# FPGA.net
KiCad netlist of a schematic drawn in Altium Designer
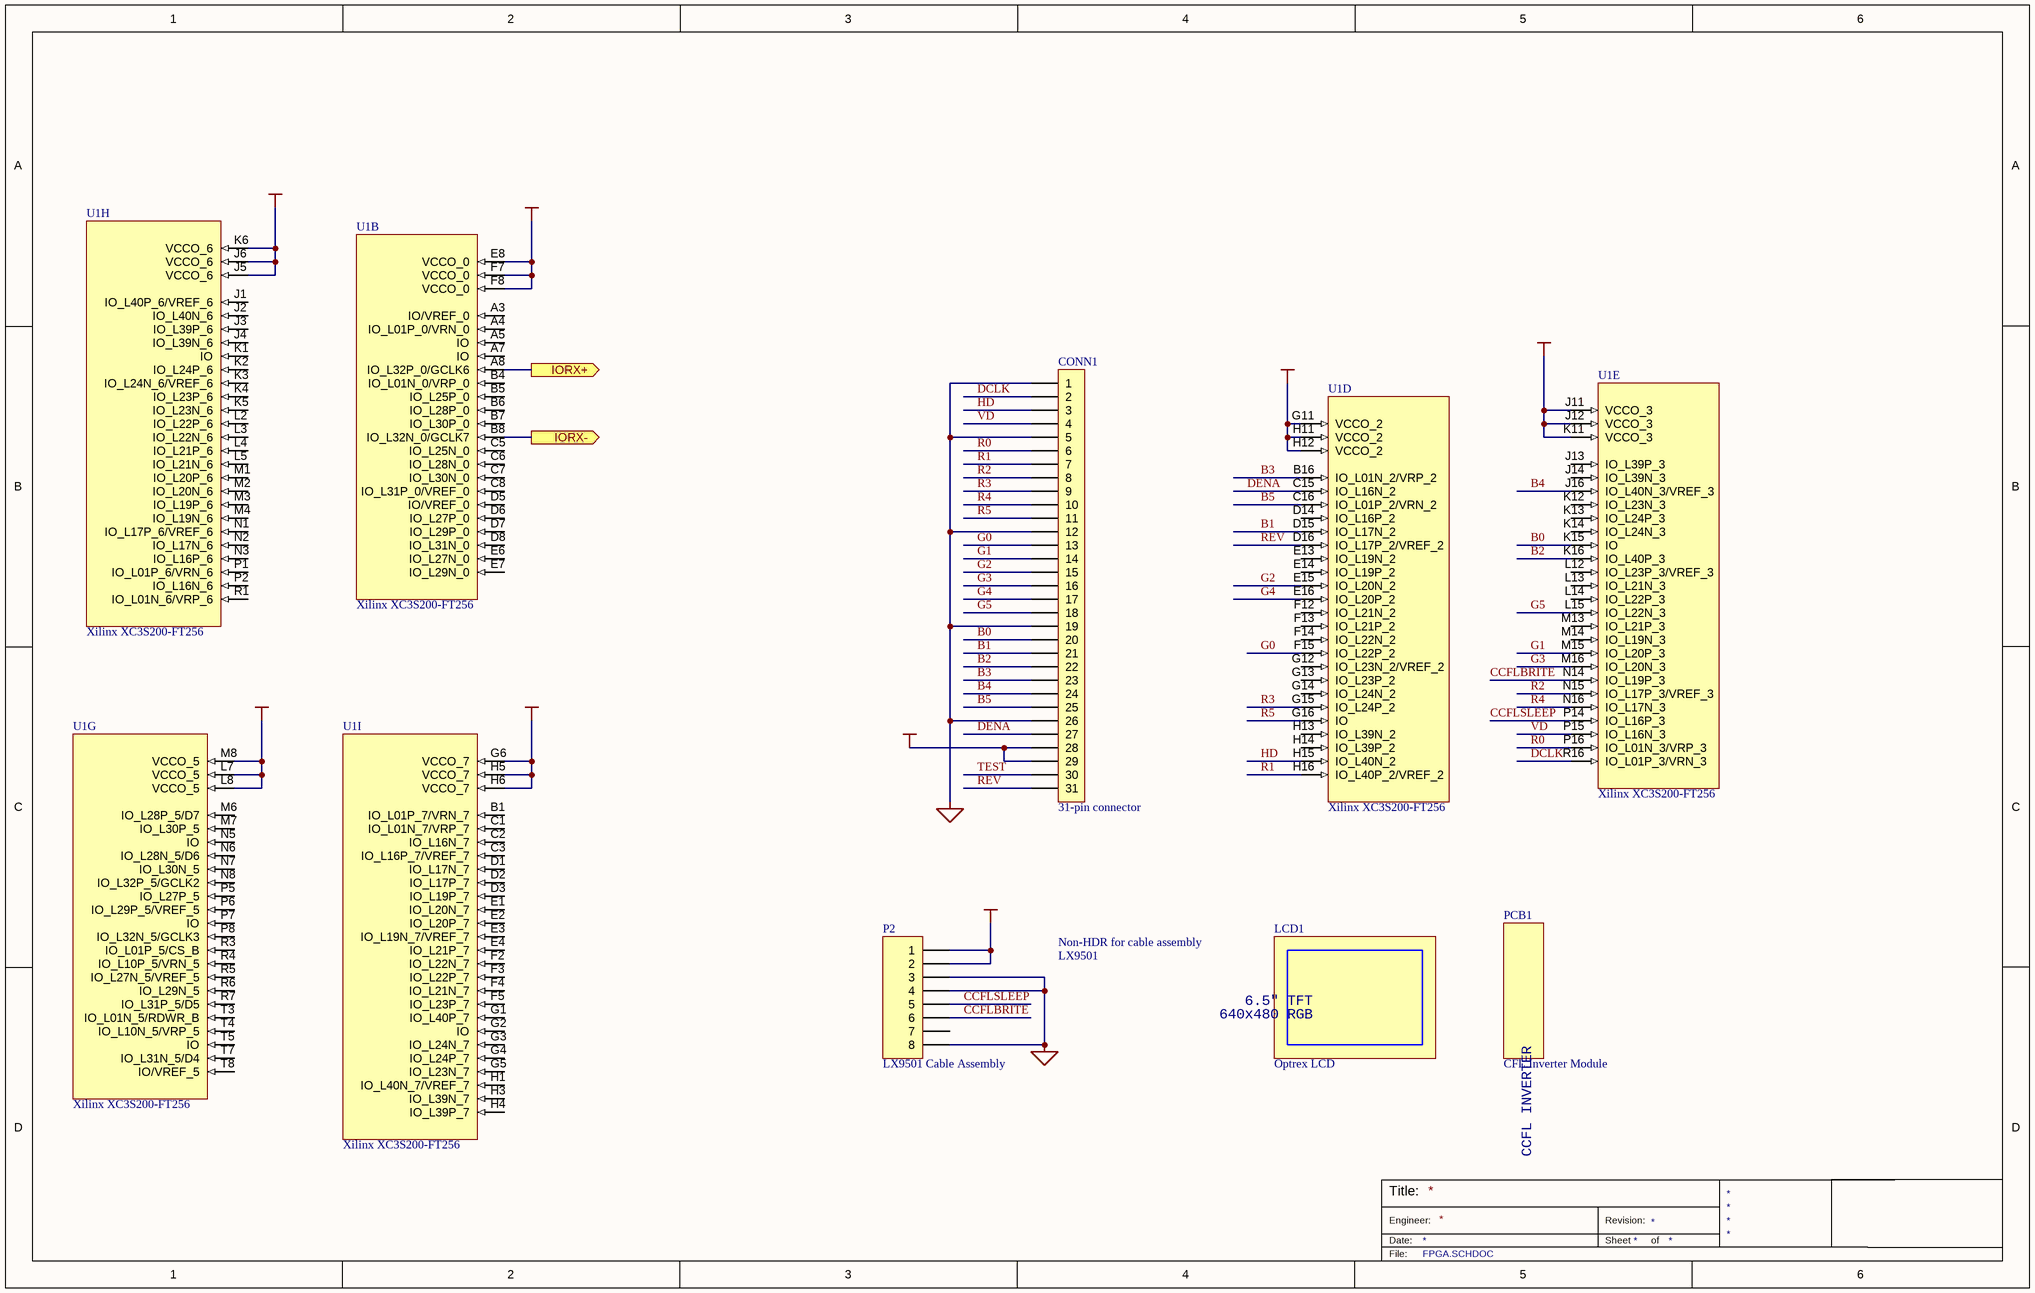
[diagram p0: FPGA.SCHDOC]

(export (version "E")
  (design (tool "Eeschema 10.0.6"))
  (components
    (comp (ref "CONN1")
      (value "31-pin connector")
      (footprint "DF9A-31S-1V")
      (libsource (lib "*") (part "CON31"))
    )
    (comp (ref "LCD1")
      (value "Optrex LCD")
      (description "Optrex 6.5\" 640x480 TFT")
      (libsource (lib "parts") (part "T-51750GD065J-FW-AA"))
    )
    (comp (ref "P2")
      (value "LX9501 Cable Assembly")
      (footprint "HDR1X8")
      (description "Header, 8-Pin")
      (fields (field (name "PUBLISHER") "Altium Limited"))
      (libsource (lib "Miscellaneous Connectors") (part "Header 8"))
    )
    (comp (ref "PCB1")
      (value "CFL Inverter Module")
      (description "4W 12V Inverter module for CCFL")
      (libsource (lib "parts") (part "LXM1623-12-41"))
    )
    (comp (ref "U1")
      (value "Xilinx XC3S200-FT256")
      (footprint "Xilinx FT256 BGA")
      (description "Xilinx Spartan-3 FPGA")
      (libsource (lib "parts") (part "XC3S200-FT256"))
    )
  )
  (nets
    (net (code "1") (name "+2.5VCC") (class "Default")
      (node (ref "U1") (pin "E8") (pinfunction "VCCO_0_E8") (pintype "input"))
      (node (ref "U1") (pin "F7") (pinfunction "VCCO_0_F7") (pintype "input"))
      (node (ref "U1") (pin "F8") (pinfunction "VCCO_0_F8") (pintype "input"))
    )
    (net (code "2") (name "+12VCC") (class "Default")
      (node (ref "P2") (pin "1") (pinfunction "1_1") (pintype "passive"))
      (node (ref "P2") (pin "2") (pinfunction "2_2") (pintype "passive"))
    )
    (net (code "3") (name "/B0") (class "Default")
      (node (ref "CONN1") (pin "20") (pinfunction "20_20") (pintype "passive"))
      (node (ref "U1") (pin "K15") (pinfunction "IO_K15") (pintype "input"))
    )
    (net (code "4") (name "/B1") (class "Default")
      (node (ref "CONN1") (pin "21") (pinfunction "21_21") (pintype "passive"))
      (node (ref "U1") (pin "D15") (pinfunction "IO_L17N_2_D15") (pintype "input"))
    )
    (net (code "5") (name "/B2") (class "Default")
      (node (ref "CONN1") (pin "22") (pinfunction "22_22") (pintype "passive"))
      (node (ref "U1") (pin "K16") (pinfunction "IO_L40P_3_K16") (pintype "input"))
    )
    (net (code "6") (name "/B3") (class "Default")
      (node (ref "CONN1") (pin "23") (pinfunction "23_23") (pintype "passive"))
      (node (ref "U1") (pin "B16") (pinfunction "IO_L01N_2/VRP_2_B16") (pintype "input"))
    )
    (net (code "7") (name "/B4") (class "Default")
      (node (ref "CONN1") (pin "24") (pinfunction "24_24") (pintype "passive"))
      (node (ref "U1") (pin "J16") (pinfunction "IO_L40N_3/VREF_3_J16") (pintype "input"))
    )
    (net (code "8") (name "/B5") (class "Default")
      (node (ref "CONN1") (pin "25") (pinfunction "25_25") (pintype "passive"))
      (node (ref "U1") (pin "C16") (pinfunction "IO_L01P_2/VRN_2_C16") (pintype "input"))
    )
    (net (code "9") (name "/CCFLBRITE") (class "Default")
      (node (ref "P2") (pin "6") (pinfunction "6_6") (pintype "passive"))
      (node (ref "U1") (pin "N14") (pinfunction "IO_L19P_3_N14") (pintype "input"))
    )
    (net (code "10") (name "/CCFLSLEEP") (class "Default")
      (node (ref "P2") (pin "5") (pinfunction "5_5") (pintype "passive"))
      (node (ref "U1") (pin "P14") (pinfunction "IO_L16P_3_P14") (pintype "input"))
    )
    (net (code "11") (name "/DCLK") (class "Default")
      (node (ref "CONN1") (pin "2") (pinfunction "2_2") (pintype "passive"))
      (node (ref "U1") (pin "R16") (pinfunction "IO_L01P_3/VRN_3_R16") (pintype "input"))
    )
    (net (code "12") (name "/DENA") (class "Default")
      (node (ref "CONN1") (pin "27") (pinfunction "27_27") (pintype "passive"))
      (node (ref "U1") (pin "C15") (pinfunction "IO_L16N_2_C15") (pintype "input"))
    )
    (net (code "13") (name "/G0") (class "Default")
      (node (ref "CONN1") (pin "13") (pinfunction "13_13") (pintype "passive"))
      (node (ref "U1") (pin "F15") (pinfunction "IO_L22P_2_F15") (pintype "input"))
    )
    (net (code "14") (name "/G1") (class "Default")
      (node (ref "CONN1") (pin "14") (pinfunction "14_14") (pintype "passive"))
      (node (ref "U1") (pin "M15") (pinfunction "IO_L20P_3_M15") (pintype "input"))
    )
    (net (code "15") (name "/G2") (class "Default")
      (node (ref "CONN1") (pin "15") (pinfunction "15_15") (pintype "passive"))
      (node (ref "U1") (pin "E15") (pinfunction "IO_L20N_2_E15") (pintype "input"))
    )
    (net (code "16") (name "/G3") (class "Default")
      (node (ref "CONN1") (pin "16") (pinfunction "16_16") (pintype "passive"))
      (node (ref "U1") (pin "M16") (pinfunction "IO_L20N_3_M16") (pintype "input"))
    )
    (net (code "17") (name "/G4") (class "Default")
      (node (ref "CONN1") (pin "17") (pinfunction "17_17") (pintype "passive"))
      (node (ref "U1") (pin "E16") (pinfunction "IO_L20P_2_E16") (pintype "input"))
    )
    (net (code "18") (name "/G5") (class "Default")
      (node (ref "CONN1") (pin "18") (pinfunction "18_18") (pintype "passive"))
      (node (ref "U1") (pin "L15") (pinfunction "IO_L22N_3_L15") (pintype "input"))
    )
    (net (code "19") (name "/HD") (class "Default")
      (node (ref "CONN1") (pin "3") (pinfunction "3_3") (pintype "passive"))
      (node (ref "U1") (pin "H15") (pinfunction "IO_L40N_2_H15") (pintype "input"))
    )
    (net (code "20") (name "/IORX+") (class "Default")
      (node (ref "U1") (pin "A8") (pinfunction "IO_L32P_0/GCLK6_A8") (pintype "input"))
    )
    (net (code "21") (name "/IORX-") (class "Default")
      (node (ref "U1") (pin "B8") (pinfunction "IO_L32N_0/GCLK7_B8") (pintype "input"))
    )
    (net (code "22") (name "/R0") (class "Default")
      (node (ref "CONN1") (pin "6") (pinfunction "6_6") (pintype "passive"))
      (node (ref "U1") (pin "P16") (pinfunction "IO_L01N_3/VRP_3_P16") (pintype "input"))
    )
    (net (code "23") (name "/R1") (class "Default")
      (node (ref "CONN1") (pin "7") (pinfunction "7_7") (pintype "passive"))
      (node (ref "U1") (pin "H16") (pinfunction "IO_L40P_2/VREF_2_H16") (pintype "input"))
    )
    (net (code "24") (name "/R2") (class "Default")
      (node (ref "CONN1") (pin "8") (pinfunction "8_8") (pintype "passive"))
      (node (ref "U1") (pin "N15") (pinfunction "IO_L17P_3/VREF_3_N15") (pintype "input"))
    )
    (net (code "25") (name "/R3") (class "Default")
      (node (ref "CONN1") (pin "9") (pinfunction "9_9") (pintype "passive"))
      (node (ref "U1") (pin "G15") (pinfunction "IO_L24P_2_G15") (pintype "input"))
    )
    (net (code "26") (name "/R4") (class "Default")
      (node (ref "CONN1") (pin "10") (pinfunction "10_10") (pintype "passive"))
      (node (ref "U1") (pin "N16") (pinfunction "IO_L17N_3_N16") (pintype "input"))
    )
    (net (code "27") (name "/R5") (class "Default")
      (node (ref "CONN1") (pin "11") (pinfunction "11_11") (pintype "passive"))
      (node (ref "U1") (pin "G16") (pinfunction "IO_G16") (pintype "input"))
    )
    (net (code "28") (name "/REV") (class "Default")
      (node (ref "CONN1") (pin "31") (pinfunction "31_31") (pintype "passive"))
      (node (ref "U1") (pin "D16") (pinfunction "IO_L17P_2/VREF_2_D16") (pintype "input"))
    )
    (net (code "29") (name "/TEST") (class "Default")
      (node (ref "CONN1") (pin "30") (pinfunction "30_30") (pintype "passive"))
    )
    (net (code "30") (name "/VD") (class "Default")
      (node (ref "CONN1") (pin "4") (pinfunction "4_4") (pintype "passive"))
      (node (ref "U1") (pin "P15") (pinfunction "IO_L16N_3_P15") (pintype "input"))
    )
    (net (code "31") (name "GND") (class "Default")
      (node (ref "CONN1") (pin "1") (pinfunction "1_1") (pintype "passive"))
      (node (ref "CONN1") (pin "12") (pinfunction "12_12") (pintype "passive"))
      (node (ref "CONN1") (pin "19") (pinfunction "19_19") (pintype "passive"))
      (node (ref "CONN1") (pin "26") (pinfunction "26_26") (pintype "passive"))
      (node (ref "CONN1") (pin "5") (pinfunction "5_5") (pintype "passive"))
      (node (ref "P2") (pin "3") (pinfunction "3_3") (pintype "passive"))
      (node (ref "P2") (pin "4") (pinfunction "4_4") (pintype "passive"))
      (node (ref "P2") (pin "8") (pinfunction "8_8") (pintype "passive"))
    )
    (net (code "32") (name "VCC") (class "Default")
      (node (ref "CONN1") (pin "28") (pinfunction "28_28") (pintype "passive"))
      (node (ref "CONN1") (pin "29") (pinfunction "29_29") (pintype "passive"))
      (node (ref "U1") (pin "G11") (pinfunction "VCCO_2_G11") (pintype "input"))
      (node (ref "U1") (pin "G6") (pinfunction "VCCO_7_G6") (pintype "input"))
      (node (ref "U1") (pin "H11") (pinfunction "VCCO_2_H11") (pintype "input"))
      (node (ref "U1") (pin "H12") (pinfunction "VCCO_2_H12") (pintype "input"))
      (node (ref "U1") (pin "H5") (pinfunction "VCCO_7_H5") (pintype "input"))
      (node (ref "U1") (pin "H6") (pinfunction "VCCO_7_H6") (pintype "input"))
      (node (ref "U1") (pin "J11") (pinfunction "VCCO_3_J11") (pintype "input"))
      (node (ref "U1") (pin "J12") (pinfunction "VCCO_3_J12") (pintype "input"))
      (node (ref "U1") (pin "J5") (pinfunction "VCCO_6_J5") (pintype "input"))
      (node (ref "U1") (pin "J6") (pinfunction "VCCO_6_J6") (pintype "input"))
      (node (ref "U1") (pin "K11") (pinfunction "VCCO_3_K11") (pintype "input"))
      (node (ref "U1") (pin "K6") (pinfunction "VCCO_6_K6") (pintype "input"))
      (node (ref "U1") (pin "L7") (pinfunction "VCCO_5_L7") (pintype "input"))
      (node (ref "U1") (pin "L8") (pinfunction "VCCO_5_L8") (pintype "input"))
      (node (ref "U1") (pin "M8") (pinfunction "VCCO_5_M8") (pintype "input"))
    )
    (net (code "33") (name "unconnected-(P2-Pad7)") (class "Default")
      (node (ref "P2") (pin "7") (pinfunction "7_7") (pintype "passive"))
    )
    (net (code "34") (name "unconnected-(U1B-IO-PadA5)") (class "Default")
      (node (ref "U1") (pin "A5") (pinfunction "IO_A5") (pintype "input"))
    )
    (net (code "35") (name "unconnected-(U1B-IO-PadA7)") (class "Default")
      (node (ref "U1") (pin "A7") (pinfunction "IO_A7") (pintype "input"))
    )
    (net (code "36") (name "unconnected-(U1B-IO_L01N_0{slash}VRP_0-PadB4)") (class "Default")
      (node (ref "U1") (pin "B4") (pinfunction "IO_L01N_0/VRP_0_B4") (pintype "input"))
    )
    (net (code "37") (name "unconnected-(U1B-IO_L01P_0{slash}VRN_0-PadA4)") (class "Default")
      (node (ref "U1") (pin "A4") (pinfunction "IO_L01P_0/VRN_0_A4") (pintype "input"))
    )
    (net (code "38") (name "unconnected-(U1B-IO_L25N_0-PadC5)") (class "Default")
      (node (ref "U1") (pin "C5") (pinfunction "IO_L25N_0_C5") (pintype "input"))
    )
    (net (code "39") (name "unconnected-(U1B-IO_L25P_0-PadB5)") (class "Default")
      (node (ref "U1") (pin "B5") (pinfunction "IO_L25P_0_B5") (pintype "input"))
    )
    (net (code "40") (name "unconnected-(U1B-IO_L27N_0-PadE6)") (class "Default")
      (node (ref "U1") (pin "E6") (pinfunction "IO_L27N_0_E6") (pintype "input"))
    )
    (net (code "41") (name "unconnected-(U1B-IO_L27P_0-PadD6)") (class "Default")
      (node (ref "U1") (pin "D6") (pinfunction "IO_L27P_0_D6") (pintype "input"))
    )
    (net (code "42") (name "unconnected-(U1B-IO_L28N_0-PadC6)") (class "Default")
      (node (ref "U1") (pin "C6") (pinfunction "IO_L28N_0_C6") (pintype "input"))
    )
    (net (code "43") (name "unconnected-(U1B-IO_L28P_0-PadB6)") (class "Default")
      (node (ref "U1") (pin "B6") (pinfunction "IO_L28P_0_B6") (pintype "input"))
    )
    (net (code "44") (name "unconnected-(U1B-IO_L29N_0-PadE7)") (class "Default")
      (node (ref "U1") (pin "E7") (pinfunction "IO_L29N_0_E7") (pintype "input"))
    )
    (net (code "45") (name "unconnected-(U1B-IO_L29P_0-PadD7)") (class "Default")
      (node (ref "U1") (pin "D7") (pinfunction "IO_L29P_0_D7") (pintype "input"))
    )
    (net (code "46") (name "unconnected-(U1B-IO_L30N_0-PadC7)") (class "Default")
      (node (ref "U1") (pin "C7") (pinfunction "IO_L30N_0_C7") (pintype "input"))
    )
    (net (code "47") (name "unconnected-(U1B-IO_L30P_0-PadB7)") (class "Default")
      (node (ref "U1") (pin "B7") (pinfunction "IO_L30P_0_B7") (pintype "input"))
    )
    (net (code "48") (name "unconnected-(U1B-IO_L31N_0-PadD8)") (class "Default")
      (node (ref "U1") (pin "D8") (pinfunction "IO_L31N_0_D8") (pintype "input"))
    )
    (net (code "49") (name "unconnected-(U1B-IO_L31P_0{slash}VREF_0-PadC8)") (class "Default")
      (node (ref "U1") (pin "C8") (pinfunction "IO_L31P_0/VREF_0_C8") (pintype "input"))
    )
    (net (code "50") (name "unconnected-(U1B-IO{slash}VREF_0-PadA3)") (class "Default")
      (node (ref "U1") (pin "A3") (pinfunction "IO/VREF_0_A3") (pintype "input"))
    )
    (net (code "51") (name "unconnected-(U1B-IO{slash}VREF_0-PadD5)") (class "Default")
      (node (ref "U1") (pin "D5") (pinfunction "IO/VREF_0_D5") (pintype "input"))
    )
    (net (code "52") (name "unconnected-(U1D-IO_L16P_2-PadD14)") (class "Default")
      (node (ref "U1") (pin "D14") (pinfunction "IO_L16P_2_D14") (pintype "input"))
    )
    (net (code "53") (name "unconnected-(U1D-IO_L19N_2-PadE13)") (class "Default")
      (node (ref "U1") (pin "E13") (pinfunction "IO_L19N_2_E13") (pintype "input"))
    )
    (net (code "54") (name "unconnected-(U1D-IO_L19P_2-PadE14)") (class "Default")
      (node (ref "U1") (pin "E14") (pinfunction "IO_L19P_2_E14") (pintype "input"))
    )
    (net (code "55") (name "unconnected-(U1D-IO_L21N_2-PadF12)") (class "Default")
      (node (ref "U1") (pin "F12") (pinfunction "IO_L21N_2_F12") (pintype "input"))
    )
    (net (code "56") (name "unconnected-(U1D-IO_L21P_2-PadF13)") (class "Default")
      (node (ref "U1") (pin "F13") (pinfunction "IO_L21P_2_F13") (pintype "input"))
    )
    (net (code "57") (name "unconnected-(U1D-IO_L22N_2-PadF14)") (class "Default")
      (node (ref "U1") (pin "F14") (pinfunction "IO_L22N_2_F14") (pintype "input"))
    )
    (net (code "58") (name "unconnected-(U1D-IO_L23N_2{slash}VREF_2-PadG12)") (class "Default")
      (node (ref "U1") (pin "G12") (pinfunction "IO_L23N_2/VREF_2_G12") (pintype "input"))
    )
    (net (code "59") (name "unconnected-(U1D-IO_L23P_2-PadG13)") (class "Default")
      (node (ref "U1") (pin "G13") (pinfunction "IO_L23P_2_G13") (pintype "input"))
    )
    (net (code "60") (name "unconnected-(U1D-IO_L24N_2-PadG14)") (class "Default")
      (node (ref "U1") (pin "G14") (pinfunction "IO_L24N_2_G14") (pintype "input"))
    )
    (net (code "61") (name "unconnected-(U1D-IO_L39N_2-PadH13)") (class "Default")
      (node (ref "U1") (pin "H13") (pinfunction "IO_L39N_2_H13") (pintype "input"))
    )
    (net (code "62") (name "unconnected-(U1D-IO_L39P_2-PadH14)") (class "Default")
      (node (ref "U1") (pin "H14") (pinfunction "IO_L39P_2_H14") (pintype "input"))
    )
    (net (code "63") (name "unconnected-(U1E-IO_L19N_3-PadM14)") (class "Default")
      (node (ref "U1") (pin "M14") (pinfunction "IO_L19N_3_M14") (pintype "input"))
    )
    (net (code "64") (name "unconnected-(U1E-IO_L21N_3-PadL13)") (class "Default")
      (node (ref "U1") (pin "L13") (pinfunction "IO_L21N_3_L13") (pintype "input"))
    )
    (net (code "65") (name "unconnected-(U1E-IO_L21P_3-PadM13)") (class "Default")
      (node (ref "U1") (pin "M13") (pinfunction "IO_L21P_3_M13") (pintype "input"))
    )
    (net (code "66") (name "unconnected-(U1E-IO_L22P_3-PadL14)") (class "Default")
      (node (ref "U1") (pin "L14") (pinfunction "IO_L22P_3_L14") (pintype "input"))
    )
    (net (code "67") (name "unconnected-(U1E-IO_L23N_3-PadK12)") (class "Default")
      (node (ref "U1") (pin "K12") (pinfunction "IO_L23N_3_K12") (pintype "input"))
    )
    (net (code "68") (name "unconnected-(U1E-IO_L23P_3{slash}VREF_3-PadL12)") (class "Default")
      (node (ref "U1") (pin "L12") (pinfunction "IO_L23P_3/VREF_3_L12") (pintype "input"))
    )
    (net (code "69") (name "unconnected-(U1E-IO_L24N_3-PadK14)") (class "Default")
      (node (ref "U1") (pin "K14") (pinfunction "IO_L24N_3_K14") (pintype "input"))
    )
    (net (code "70") (name "unconnected-(U1E-IO_L24P_3-PadK13)") (class "Default")
      (node (ref "U1") (pin "K13") (pinfunction "IO_L24P_3_K13") (pintype "input"))
    )
    (net (code "71") (name "unconnected-(U1E-IO_L39N_3-PadJ14)") (class "Default")
      (node (ref "U1") (pin "J14") (pinfunction "IO_L39N_3_J14") (pintype "input"))
    )
    (net (code "72") (name "unconnected-(U1E-IO_L39P_3-PadJ13)") (class "Default")
      (node (ref "U1") (pin "J13") (pinfunction "IO_L39P_3_J13") (pintype "input"))
    )
    (net (code "73") (name "unconnected-(U1G-IO-PadN5)") (class "Default")
      (node (ref "U1") (pin "N5") (pinfunction "IO_N5") (pintype "input"))
    )
    (net (code "74") (name "unconnected-(U1G-IO-PadP7)") (class "Default")
      (node (ref "U1") (pin "P7") (pinfunction "IO_P7") (pintype "input"))
    )
    (net (code "75") (name "unconnected-(U1G-IO-PadT5)") (class "Default")
      (node (ref "U1") (pin "T5") (pinfunction "IO_T5") (pintype "input"))
    )
    (net (code "76") (name "unconnected-(U1G-IO_L01N_5{slash}RDWR_B-PadT3)") (class "Default")
      (node (ref "U1") (pin "T3") (pinfunction "IO_L01N_5/RDWR_B_T3") (pintype "input"))
    )
    (net (code "77") (name "unconnected-(U1G-IO_L01P_5{slash}CS_B-PadR3)") (class "Default")
      (node (ref "U1") (pin "R3") (pinfunction "IO_L01P_5/CS_B_R3") (pintype "input"))
    )
    (net (code "78") (name "unconnected-(U1G-IO_L10N_5{slash}VRP_5-PadT4)") (class "Default")
      (node (ref "U1") (pin "T4") (pinfunction "IO_L10N_5/VRP_5_T4") (pintype "input"))
    )
    (net (code "79") (name "unconnected-(U1G-IO_L10P_5{slash}VRN_5-PadR4)") (class "Default")
      (node (ref "U1") (pin "R4") (pinfunction "IO_L10P_5/VRN_5_R4") (pintype "input"))
    )
    (net (code "80") (name "unconnected-(U1G-IO_L27N_5{slash}VREF_5-PadR5)") (class "Default")
      (node (ref "U1") (pin "R5") (pinfunction "IO_L27N_5/VREF_5_R5") (pintype "input"))
    )
    (net (code "81") (name "unconnected-(U1G-IO_L27P_5-PadP5)") (class "Default")
      (node (ref "U1") (pin "P5") (pinfunction "IO_L27P_5_P5") (pintype "input"))
    )
    (net (code "82") (name "unconnected-(U1G-IO_L28N_5{slash}D6-PadN6)") (class "Default")
      (node (ref "U1") (pin "N6") (pinfunction "IO_L28N_5/D6_N6") (pintype "input"))
    )
    (net (code "83") (name "unconnected-(U1G-IO_L28P_5{slash}D7-PadM6)") (class "Default")
      (node (ref "U1") (pin "M6") (pinfunction "IO_L28P_5/D7_M6") (pintype "input"))
    )
    (net (code "84") (name "unconnected-(U1G-IO_L29N_5-PadR6)") (class "Default")
      (node (ref "U1") (pin "R6") (pinfunction "IO_L29N_5_R6") (pintype "input"))
    )
    (net (code "85") (name "unconnected-(U1G-IO_L29P_5{slash}VREF_5-PadP6)") (class "Default")
      (node (ref "U1") (pin "P6") (pinfunction "IO_L29P_5/VREF_5_P6") (pintype "input"))
    )
    (net (code "86") (name "unconnected-(U1G-IO_L30N_5-PadN7)") (class "Default")
      (node (ref "U1") (pin "N7") (pinfunction "IO_L30N_5_N7") (pintype "input"))
    )
    (net (code "87") (name "unconnected-(U1G-IO_L30P_5-PadM7)") (class "Default")
      (node (ref "U1") (pin "M7") (pinfunction "IO_L30P_5_M7") (pintype "input"))
    )
    (net (code "88") (name "unconnected-(U1G-IO_L31N_5{slash}D4-PadT7)") (class "Default")
      (node (ref "U1") (pin "T7") (pinfunction "IO_L31N_5/D4_T7") (pintype "input"))
    )
    (net (code "89") (name "unconnected-(U1G-IO_L31P_5{slash}D5-PadR7)") (class "Default")
      (node (ref "U1") (pin "R7") (pinfunction "IO_L31P_5/D5_R7") (pintype "input"))
    )
    (net (code "90") (name "unconnected-(U1G-IO_L32N_5{slash}GCLK3-PadP8)") (class "Default")
      (node (ref "U1") (pin "P8") (pinfunction "IO_L32N_5/GCLK3_P8") (pintype "input"))
    )
    (net (code "91") (name "unconnected-(U1G-IO_L32P_5{slash}GCLK2-PadN8)") (class "Default")
      (node (ref "U1") (pin "N8") (pinfunction "IO_L32P_5/GCLK2_N8") (pintype "input"))
    )
    (net (code "92") (name "unconnected-(U1G-IO{slash}VREF_5-PadT8)") (class "Default")
      (node (ref "U1") (pin "T8") (pinfunction "IO/VREF_5_T8") (pintype "input"))
    )
    (net (code "93") (name "unconnected-(U1H-IO-PadK1)") (class "Default")
      (node (ref "U1") (pin "K1") (pinfunction "IO_K1") (pintype "input"))
    )
    (net (code "94") (name "unconnected-(U1H-IO_L01N_6{slash}VRP_6-PadR1)") (class "Default")
      (node (ref "U1") (pin "R1") (pinfunction "IO_L01N_6/VRP_6_R1") (pintype "input"))
    )
    (net (code "95") (name "unconnected-(U1H-IO_L01P_6{slash}VRN_6-PadP1)") (class "Default")
      (node (ref "U1") (pin "P1") (pinfunction "IO_L01P_6/VRN_6_P1") (pintype "input"))
    )
    (net (code "96") (name "unconnected-(U1H-IO_L16N_6-PadP2)") (class "Default")
      (node (ref "U1") (pin "P2") (pinfunction "IO_L16N_6_P2") (pintype "input"))
    )
    (net (code "97") (name "unconnected-(U1H-IO_L16P_6-PadN3)") (class "Default")
      (node (ref "U1") (pin "N3") (pinfunction "IO_L16P_6_N3") (pintype "input"))
    )
    (net (code "98") (name "unconnected-(U1H-IO_L17N_6-PadN2)") (class "Default")
      (node (ref "U1") (pin "N2") (pinfunction "IO_L17N_6_N2") (pintype "input"))
    )
    (net (code "99") (name "unconnected-(U1H-IO_L17P_6{slash}VREF_6-PadN1)") (class "Default")
      (node (ref "U1") (pin "N1") (pinfunction "IO_L17P_6/VREF_6_N1") (pintype "input"))
    )
    (net (code "100") (name "unconnected-(U1H-IO_L19N_6-PadM4)") (class "Default")
      (node (ref "U1") (pin "M4") (pinfunction "IO_L19N_6_M4") (pintype "input"))
    )
    (net (code "101") (name "unconnected-(U1H-IO_L19P_6-PadM3)") (class "Default")
      (node (ref "U1") (pin "M3") (pinfunction "IO_L19P_6_M3") (pintype "input"))
    )
    (net (code "102") (name "unconnected-(U1H-IO_L20N_6-PadM2)") (class "Default")
      (node (ref "U1") (pin "M2") (pinfunction "IO_L20N_6_M2") (pintype "input"))
    )
    (net (code "103") (name "unconnected-(U1H-IO_L20P_6-PadM1)") (class "Default")
      (node (ref "U1") (pin "M1") (pinfunction "IO_L20P_6_M1") (pintype "input"))
    )
    (net (code "104") (name "unconnected-(U1H-IO_L21N_6-PadL5)") (class "Default")
      (node (ref "U1") (pin "L5") (pinfunction "IO_L21N_6_L5") (pintype "input"))
    )
    (net (code "105") (name "unconnected-(U1H-IO_L21P_6-PadL4)") (class "Default")
      (node (ref "U1") (pin "L4") (pinfunction "IO_L21P_6_L4") (pintype "input"))
    )
    (net (code "106") (name "unconnected-(U1H-IO_L22N_6-PadL3)") (class "Default")
      (node (ref "U1") (pin "L3") (pinfunction "IO_L22N_6_L3") (pintype "input"))
    )
    (net (code "107") (name "unconnected-(U1H-IO_L22P_6-PadL2)") (class "Default")
      (node (ref "U1") (pin "L2") (pinfunction "IO_L22P_6_L2") (pintype "input"))
    )
    (net (code "108") (name "unconnected-(U1H-IO_L23N_6-PadK5)") (class "Default")
      (node (ref "U1") (pin "K5") (pinfunction "IO_L23N_6_K5") (pintype "input"))
    )
    (net (code "109") (name "unconnected-(U1H-IO_L23P_6-PadK4)") (class "Default")
      (node (ref "U1") (pin "K4") (pinfunction "IO_L23P_6_K4") (pintype "input"))
    )
    (net (code "110") (name "unconnected-(U1H-IO_L24N_6{slash}VREF_6-PadK3)") (class "Default")
      (node (ref "U1") (pin "K3") (pinfunction "IO_L24N_6/VREF_6_K3") (pintype "input"))
    )
    (net (code "111") (name "unconnected-(U1H-IO_L24P_6-PadK2)") (class "Default")
      (node (ref "U1") (pin "K2") (pinfunction "IO_L24P_6_K2") (pintype "input"))
    )
    (net (code "112") (name "unconnected-(U1H-IO_L39N_6-PadJ4)") (class "Default")
      (node (ref "U1") (pin "J4") (pinfunction "IO_L39N_6_J4") (pintype "input"))
    )
    (net (code "113") (name "unconnected-(U1H-IO_L39P_6-PadJ3)") (class "Default")
      (node (ref "U1") (pin "J3") (pinfunction "IO_L39P_6_J3") (pintype "input"))
    )
    (net (code "114") (name "unconnected-(U1H-IO_L40N_6-PadJ2)") (class "Default")
      (node (ref "U1") (pin "J2") (pinfunction "IO_L40N_6_J2") (pintype "input"))
    )
    (net (code "115") (name "unconnected-(U1H-IO_L40P_6{slash}VREF_6-PadJ1)") (class "Default")
      (node (ref "U1") (pin "J1") (pinfunction "IO_L40P_6/VREF_6_J1") (pintype "input"))
    )
    (net (code "116") (name "unconnected-(U1I-IO-PadG2)") (class "Default")
      (node (ref "U1") (pin "G2") (pinfunction "IO_G2") (pintype "input"))
    )
    (net (code "117") (name "unconnected-(U1I-IO_L01N_7{slash}VRP_7-PadC1)") (class "Default")
      (node (ref "U1") (pin "C1") (pinfunction "IO_L01N_7/VRP_7_C1") (pintype "input"))
    )
    (net (code "118") (name "unconnected-(U1I-IO_L01P_7{slash}VRN_7-PadB1)") (class "Default")
      (node (ref "U1") (pin "B1") (pinfunction "IO_L01P_7/VRN_7_B1") (pintype "input"))
    )
    (net (code "119") (name "unconnected-(U1I-IO_L16N_7-PadC2)") (class "Default")
      (node (ref "U1") (pin "C2") (pinfunction "IO_L16N_7_C2") (pintype "input"))
    )
    (net (code "120") (name "unconnected-(U1I-IO_L16P_7{slash}VREF_7-PadC3)") (class "Default")
      (node (ref "U1") (pin "C3") (pinfunction "IO_L16P_7/VREF_7_C3") (pintype "input"))
    )
    (net (code "121") (name "unconnected-(U1I-IO_L17N_7-PadD1)") (class "Default")
      (node (ref "U1") (pin "D1") (pinfunction "IO_L17N_7_D1") (pintype "input"))
    )
    (net (code "122") (name "unconnected-(U1I-IO_L17P_7-PadD2)") (class "Default")
      (node (ref "U1") (pin "D2") (pinfunction "IO_L17P_7_D2") (pintype "input"))
    )
    (net (code "123") (name "unconnected-(U1I-IO_L19N_7{slash}VREF_7-PadE3)") (class "Default")
      (node (ref "U1") (pin "E3") (pinfunction "IO_L19N_7/VREF_7_E3") (pintype "input"))
    )
    (net (code "124") (name "unconnected-(U1I-IO_L19P_7-PadD3)") (class "Default")
      (node (ref "U1") (pin "D3") (pinfunction "IO_L19P_7_D3") (pintype "input"))
    )
    (net (code "125") (name "unconnected-(U1I-IO_L20N_7-PadE1)") (class "Default")
      (node (ref "U1") (pin "E1") (pinfunction "IO_L20N_7_E1") (pintype "input"))
    )
    (net (code "126") (name "unconnected-(U1I-IO_L20P_7-PadE2)") (class "Default")
      (node (ref "U1") (pin "E2") (pinfunction "IO_L20P_7_E2") (pintype "input"))
    )
    (net (code "127") (name "unconnected-(U1I-IO_L21N_7-PadF4)") (class "Default")
      (node (ref "U1") (pin "F4") (pinfunction "IO_L21N_7_F4") (pintype "input"))
    )
    (net (code "128") (name "unconnected-(U1I-IO_L21P_7-PadE4)") (class "Default")
      (node (ref "U1") (pin "E4") (pinfunction "IO_L21P_7_E4") (pintype "input"))
    )
    (net (code "129") (name "unconnected-(U1I-IO_L22N_7-PadF2)") (class "Default")
      (node (ref "U1") (pin "F2") (pinfunction "IO_L22N_7_F2") (pintype "input"))
    )
    (net (code "130") (name "unconnected-(U1I-IO_L22P_7-PadF3)") (class "Default")
      (node (ref "U1") (pin "F3") (pinfunction "IO_L22P_7_F3") (pintype "input"))
    )
    (net (code "131") (name "unconnected-(U1I-IO_L23N_7-PadG5)") (class "Default")
      (node (ref "U1") (pin "G5") (pinfunction "IO_L23N_7_G5") (pintype "input"))
    )
    (net (code "132") (name "unconnected-(U1I-IO_L23P_7-PadF5)") (class "Default")
      (node (ref "U1") (pin "F5") (pinfunction "IO_L23P_7_F5") (pintype "input"))
    )
    (net (code "133") (name "unconnected-(U1I-IO_L24N_7-PadG3)") (class "Default")
      (node (ref "U1") (pin "G3") (pinfunction "IO_L24N_7_G3") (pintype "input"))
    )
    (net (code "134") (name "unconnected-(U1I-IO_L24P_7-PadG4)") (class "Default")
      (node (ref "U1") (pin "G4") (pinfunction "IO_L24P_7_G4") (pintype "input"))
    )
    (net (code "135") (name "unconnected-(U1I-IO_L39N_7-PadH3)") (class "Default")
      (node (ref "U1") (pin "H3") (pinfunction "IO_L39N_7_H3") (pintype "input"))
    )
    (net (code "136") (name "unconnected-(U1I-IO_L39P_7-PadH4)") (class "Default")
      (node (ref "U1") (pin "H4") (pinfunction "IO_L39P_7_H4") (pintype "input"))
    )
    (net (code "137") (name "unconnected-(U1I-IO_L40N_7{slash}VREF_7-PadH1)") (class "Default")
      (node (ref "U1") (pin "H1") (pinfunction "IO_L40N_7/VREF_7_H1") (pintype "input"))
    )
    (net (code "138") (name "unconnected-(U1I-IO_L40P_7-PadG1)") (class "Default")
      (node (ref "U1") (pin "G1") (pinfunction "IO_L40P_7_G1") (pintype "input"))
    )
  )
)
